# TSOP-II-44_v3_E6_6.net
KiCad netlist of a schematic drawn in EAGLE
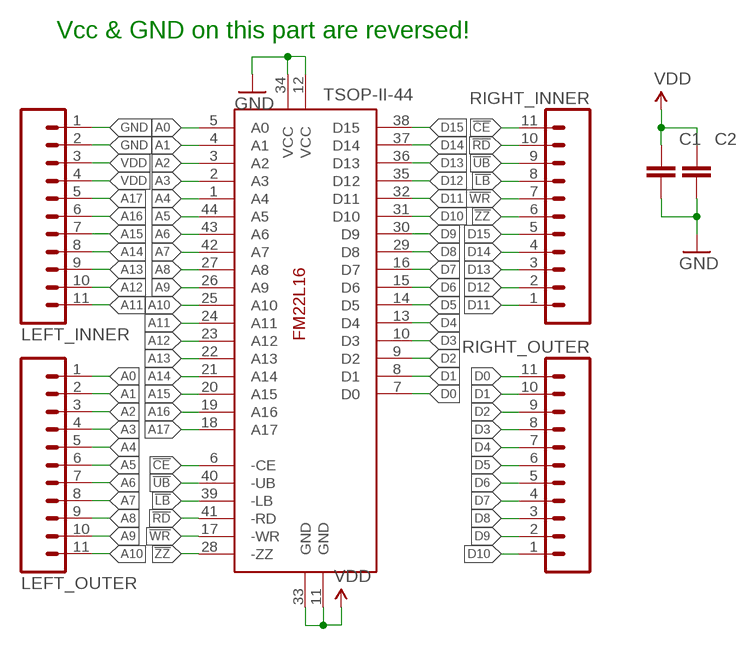
[diagram p0: schematic, sheet 1]

(export (version "E")
  (design (tool "Eeschema 10.0.6"))
  (components
    (comp (ref "C1")
      (value "CAPACITOR_NPOL-0603")
      (footprint "eagle-import:C603")
      (libsource (lib "eagle-import") (part "CAPACITOR_NPOL-0603"))
    )
    (comp (ref "C2")
      (value "CAPACITOR_NPOL-0603")
      (footprint "eagle-import:C603")
      (libsource (lib "eagle-import") (part "CAPACITOR_NPOL-0603"))
    )
    (comp (ref "LEFT_INNER")
      (value "M11PTH")
      (footprint "eagle-import:1X11")
      (libsource (lib "eagle-import") (part "M11PTH"))
    )
    (comp (ref "LEFT_OUTER")
      (value "M11PTH")
      (footprint "eagle-import:1X11")
      (libsource (lib "eagle-import") (part "M11PTH"))
    )
    (comp (ref "RIGHT_INNER")
      (value "M11PTH")
      (footprint "eagle-import:1X11")
      (libsource (lib "eagle-import") (part "M11PTH"))
    )
    (comp (ref "RIGHT_OUTER")
      (value "M11PTH")
      (footprint "eagle-import:1X11")
      (libsource (lib "eagle-import") (part "M11PTH"))
    )
    (comp (ref "TSOP-II-44")
      (value "FM22L16-TG")
      (footprint "eagle-import:TSOPII-44")
      (libsource (lib "eagle-import") (part "FM22L16-TG"))
    )
  )
  (nets
    (net (code "1") (name "/~{CE}") (class "Default")
      (node (ref "RIGHT_INNER") (pin "11") (pinfunction "11_11") (pintype "passive"))
      (node (ref "TSOP-II-44") (pin "6") (pinfunction "-CE_6") (pintype "input"))
    )
    (net (code "2") (name "/~{LB}") (class "Default")
      (node (ref "RIGHT_INNER") (pin "8") (pinfunction "8_8") (pintype "passive"))
      (node (ref "TSOP-II-44") (pin "39") (pinfunction "-LB_39") (pintype "input"))
    )
    (net (code "3") (name "/~{RD}") (class "Default")
      (node (ref "RIGHT_INNER") (pin "10") (pinfunction "10_10") (pintype "passive"))
      (node (ref "TSOP-II-44") (pin "41") (pinfunction "-RD_41") (pintype "input"))
    )
    (net (code "4") (name "/~{UB}") (class "Default")
      (node (ref "RIGHT_INNER") (pin "9") (pinfunction "9_9") (pintype "passive"))
      (node (ref "TSOP-II-44") (pin "40") (pinfunction "-UB_40") (pintype "input"))
    )
    (net (code "5") (name "/~{WR}") (class "Default")
      (node (ref "RIGHT_INNER") (pin "7") (pinfunction "7_7") (pintype "passive"))
      (node (ref "TSOP-II-44") (pin "17") (pinfunction "-WR_17") (pintype "input"))
    )
    (net (code "6") (name "/~{ZZ}") (class "Default")
      (node (ref "RIGHT_INNER") (pin "6") (pinfunction "6_6") (pintype "passive"))
      (node (ref "TSOP-II-44") (pin "28") (pinfunction "-ZZ_28") (pintype "input"))
    )
    (net (code "7") (name "A0") (class "Default")
      (node (ref "LEFT_OUTER") (pin "1") (pinfunction "1_1") (pintype "passive"))
      (node (ref "TSOP-II-44") (pin "5") (pinfunction "A0_5") (pintype "input"))
    )
    (net (code "8") (name "A1") (class "Default")
      (node (ref "LEFT_OUTER") (pin "2") (pinfunction "2_2") (pintype "passive"))
      (node (ref "TSOP-II-44") (pin "4") (pinfunction "A1_4") (pintype "input"))
    )
    (net (code "9") (name "A2") (class "Default")
      (node (ref "LEFT_OUTER") (pin "3") (pinfunction "3_3") (pintype "passive"))
      (node (ref "TSOP-II-44") (pin "3") (pinfunction "A2_3") (pintype "input"))
    )
    (net (code "10") (name "A3") (class "Default")
      (node (ref "LEFT_OUTER") (pin "4") (pinfunction "4_4") (pintype "passive"))
      (node (ref "TSOP-II-44") (pin "2") (pinfunction "A3_2") (pintype "input"))
    )
    (net (code "11") (name "A4") (class "Default")
      (node (ref "LEFT_OUTER") (pin "5") (pinfunction "5_5") (pintype "passive"))
      (node (ref "TSOP-II-44") (pin "1") (pinfunction "A4_1") (pintype "input"))
    )
    (net (code "12") (name "A5") (class "Default")
      (node (ref "LEFT_OUTER") (pin "6") (pinfunction "6_6") (pintype "passive"))
      (node (ref "TSOP-II-44") (pin "44") (pinfunction "A5_44") (pintype "input"))
    )
    (net (code "13") (name "A6") (class "Default")
      (node (ref "LEFT_OUTER") (pin "7") (pinfunction "7_7") (pintype "passive"))
      (node (ref "TSOP-II-44") (pin "43") (pinfunction "A6_43") (pintype "input"))
    )
    (net (code "14") (name "A7") (class "Default")
      (node (ref "LEFT_OUTER") (pin "8") (pinfunction "8_8") (pintype "passive"))
      (node (ref "TSOP-II-44") (pin "42") (pinfunction "A7_42") (pintype "input"))
    )
    (net (code "15") (name "A8") (class "Default")
      (node (ref "LEFT_OUTER") (pin "9") (pinfunction "9_9") (pintype "passive"))
      (node (ref "TSOP-II-44") (pin "27") (pinfunction "A8_27") (pintype "input"))
    )
    (net (code "16") (name "A9") (class "Default")
      (node (ref "LEFT_OUTER") (pin "10") (pinfunction "10_10") (pintype "passive"))
      (node (ref "TSOP-II-44") (pin "26") (pinfunction "A9_26") (pintype "input"))
    )
    (net (code "17") (name "A10") (class "Default")
      (node (ref "LEFT_OUTER") (pin "11") (pinfunction "11_11") (pintype "passive"))
      (node (ref "TSOP-II-44") (pin "25") (pinfunction "A10_25") (pintype "input"))
    )
    (net (code "18") (name "A11") (class "Default")
      (node (ref "LEFT_INNER") (pin "11") (pinfunction "11_11") (pintype "passive"))
      (node (ref "TSOP-II-44") (pin "24") (pinfunction "A11_24") (pintype "input"))
    )
    (net (code "19") (name "A12") (class "Default")
      (node (ref "LEFT_INNER") (pin "10") (pinfunction "10_10") (pintype "passive"))
      (node (ref "TSOP-II-44") (pin "23") (pinfunction "A12_23") (pintype "input"))
    )
    (net (code "20") (name "A13") (class "Default")
      (node (ref "LEFT_INNER") (pin "9") (pinfunction "9_9") (pintype "passive"))
      (node (ref "TSOP-II-44") (pin "22") (pinfunction "A13_22") (pintype "input"))
    )
    (net (code "21") (name "A14") (class "Default")
      (node (ref "LEFT_INNER") (pin "8") (pinfunction "8_8") (pintype "passive"))
      (node (ref "TSOP-II-44") (pin "21") (pinfunction "A14_21") (pintype "input"))
    )
    (net (code "22") (name "A15") (class "Default")
      (node (ref "LEFT_INNER") (pin "7") (pinfunction "7_7") (pintype "passive"))
      (node (ref "TSOP-II-44") (pin "20") (pinfunction "A15_20") (pintype "input"))
    )
    (net (code "23") (name "A16") (class "Default")
      (node (ref "LEFT_INNER") (pin "6") (pinfunction "6_6") (pintype "passive"))
      (node (ref "TSOP-II-44") (pin "19") (pinfunction "A16_19") (pintype "input"))
    )
    (net (code "24") (name "A17") (class "Default")
      (node (ref "LEFT_INNER") (pin "5") (pinfunction "5_5") (pintype "passive"))
      (node (ref "TSOP-II-44") (pin "18") (pinfunction "A17_18") (pintype "input"))
    )
    (net (code "25") (name "D0") (class "Default")
      (node (ref "RIGHT_OUTER") (pin "11") (pinfunction "11_11") (pintype "passive"))
      (node (ref "TSOP-II-44") (pin "7") (pinfunction "D0_7") (pintype "bidirectional"))
    )
    (net (code "26") (name "D1") (class "Default")
      (node (ref "RIGHT_OUTER") (pin "10") (pinfunction "10_10") (pintype "passive"))
      (node (ref "TSOP-II-44") (pin "8") (pinfunction "D1_8") (pintype "bidirectional"))
    )
    (net (code "27") (name "D2") (class "Default")
      (node (ref "RIGHT_OUTER") (pin "9") (pinfunction "9_9") (pintype "passive"))
      (node (ref "TSOP-II-44") (pin "9") (pinfunction "D2_9") (pintype "bidirectional"))
    )
    (net (code "28") (name "D3") (class "Default")
      (node (ref "RIGHT_OUTER") (pin "8") (pinfunction "8_8") (pintype "passive"))
      (node (ref "TSOP-II-44") (pin "10") (pinfunction "D3_10") (pintype "bidirectional"))
    )
    (net (code "29") (name "D4") (class "Default")
      (node (ref "RIGHT_OUTER") (pin "7") (pinfunction "7_7") (pintype "passive"))
      (node (ref "TSOP-II-44") (pin "13") (pinfunction "D4_13") (pintype "bidirectional"))
    )
    (net (code "30") (name "D5") (class "Default")
      (node (ref "RIGHT_OUTER") (pin "6") (pinfunction "6_6") (pintype "passive"))
      (node (ref "TSOP-II-44") (pin "14") (pinfunction "D5_14") (pintype "bidirectional"))
    )
    (net (code "31") (name "D6") (class "Default")
      (node (ref "RIGHT_OUTER") (pin "5") (pinfunction "5_5") (pintype "passive"))
      (node (ref "TSOP-II-44") (pin "15") (pinfunction "D6_15") (pintype "bidirectional"))
    )
    (net (code "32") (name "D7") (class "Default")
      (node (ref "RIGHT_OUTER") (pin "4") (pinfunction "4_4") (pintype "passive"))
      (node (ref "TSOP-II-44") (pin "16") (pinfunction "D7_16") (pintype "bidirectional"))
    )
    (net (code "33") (name "D8") (class "Default")
      (node (ref "RIGHT_OUTER") (pin "3") (pinfunction "3_3") (pintype "passive"))
      (node (ref "TSOP-II-44") (pin "29") (pinfunction "D8_29") (pintype "bidirectional"))
    )
    (net (code "34") (name "D9") (class "Default")
      (node (ref "RIGHT_OUTER") (pin "2") (pinfunction "2_2") (pintype "passive"))
      (node (ref "TSOP-II-44") (pin "30") (pinfunction "D9_30") (pintype "bidirectional"))
    )
    (net (code "35") (name "D10") (class "Default")
      (node (ref "RIGHT_OUTER") (pin "1") (pinfunction "1_1") (pintype "passive"))
      (node (ref "TSOP-II-44") (pin "31") (pinfunction "D10_31") (pintype "bidirectional"))
    )
    (net (code "36") (name "D11") (class "Default")
      (node (ref "RIGHT_INNER") (pin "1") (pinfunction "1_1") (pintype "passive"))
      (node (ref "TSOP-II-44") (pin "32") (pinfunction "D11_32") (pintype "bidirectional"))
    )
    (net (code "37") (name "D12") (class "Default")
      (node (ref "RIGHT_INNER") (pin "2") (pinfunction "2_2") (pintype "passive"))
      (node (ref "TSOP-II-44") (pin "35") (pinfunction "D12_35") (pintype "bidirectional"))
    )
    (net (code "38") (name "D13") (class "Default")
      (node (ref "RIGHT_INNER") (pin "3") (pinfunction "3_3") (pintype "passive"))
      (node (ref "TSOP-II-44") (pin "36") (pinfunction "D13_36") (pintype "bidirectional"))
    )
    (net (code "39") (name "D14") (class "Default")
      (node (ref "RIGHT_INNER") (pin "4") (pinfunction "4_4") (pintype "passive"))
      (node (ref "TSOP-II-44") (pin "37") (pinfunction "D14_37") (pintype "bidirectional"))
    )
    (net (code "40") (name "D15") (class "Default")
      (node (ref "RIGHT_INNER") (pin "5") (pinfunction "5_5") (pintype "passive"))
      (node (ref "TSOP-II-44") (pin "38") (pinfunction "D15_38") (pintype "bidirectional"))
    )
    (net (code "41") (name "GND") (class "Default")
      (node (ref "C1") (pin "2") (pinfunction "2_2") (pintype "passive"))
      (node (ref "C2") (pin "2") (pinfunction "2_2") (pintype "passive"))
      (node (ref "LEFT_INNER") (pin "1") (pinfunction "1_1") (pintype "passive"))
      (node (ref "LEFT_INNER") (pin "2") (pinfunction "2_2") (pintype "passive"))
      (node (ref "TSOP-II-44") (pin "12") (pinfunction "VCC_12") (pintype "power_in"))
      (node (ref "TSOP-II-44") (pin "34") (pinfunction "VCC_34") (pintype "power_in"))
    )
    (net (code "42") (name "VDD") (class "Default")
      (node (ref "C1") (pin "1") (pinfunction "1_1") (pintype "passive"))
      (node (ref "C2") (pin "1") (pinfunction "1_1") (pintype "passive"))
      (node (ref "LEFT_INNER") (pin "3") (pinfunction "3_3") (pintype "passive"))
      (node (ref "LEFT_INNER") (pin "4") (pinfunction "4_4") (pintype "passive"))
      (node (ref "TSOP-II-44") (pin "11") (pinfunction "GND_11") (pintype "power_in"))
      (node (ref "TSOP-II-44") (pin "33") (pinfunction "GND_33") (pintype "power_in"))
    )
  )
)
